# LEDboard_v0_2-R002.net
KiCad netlist of a schematic drawn in EAGLE
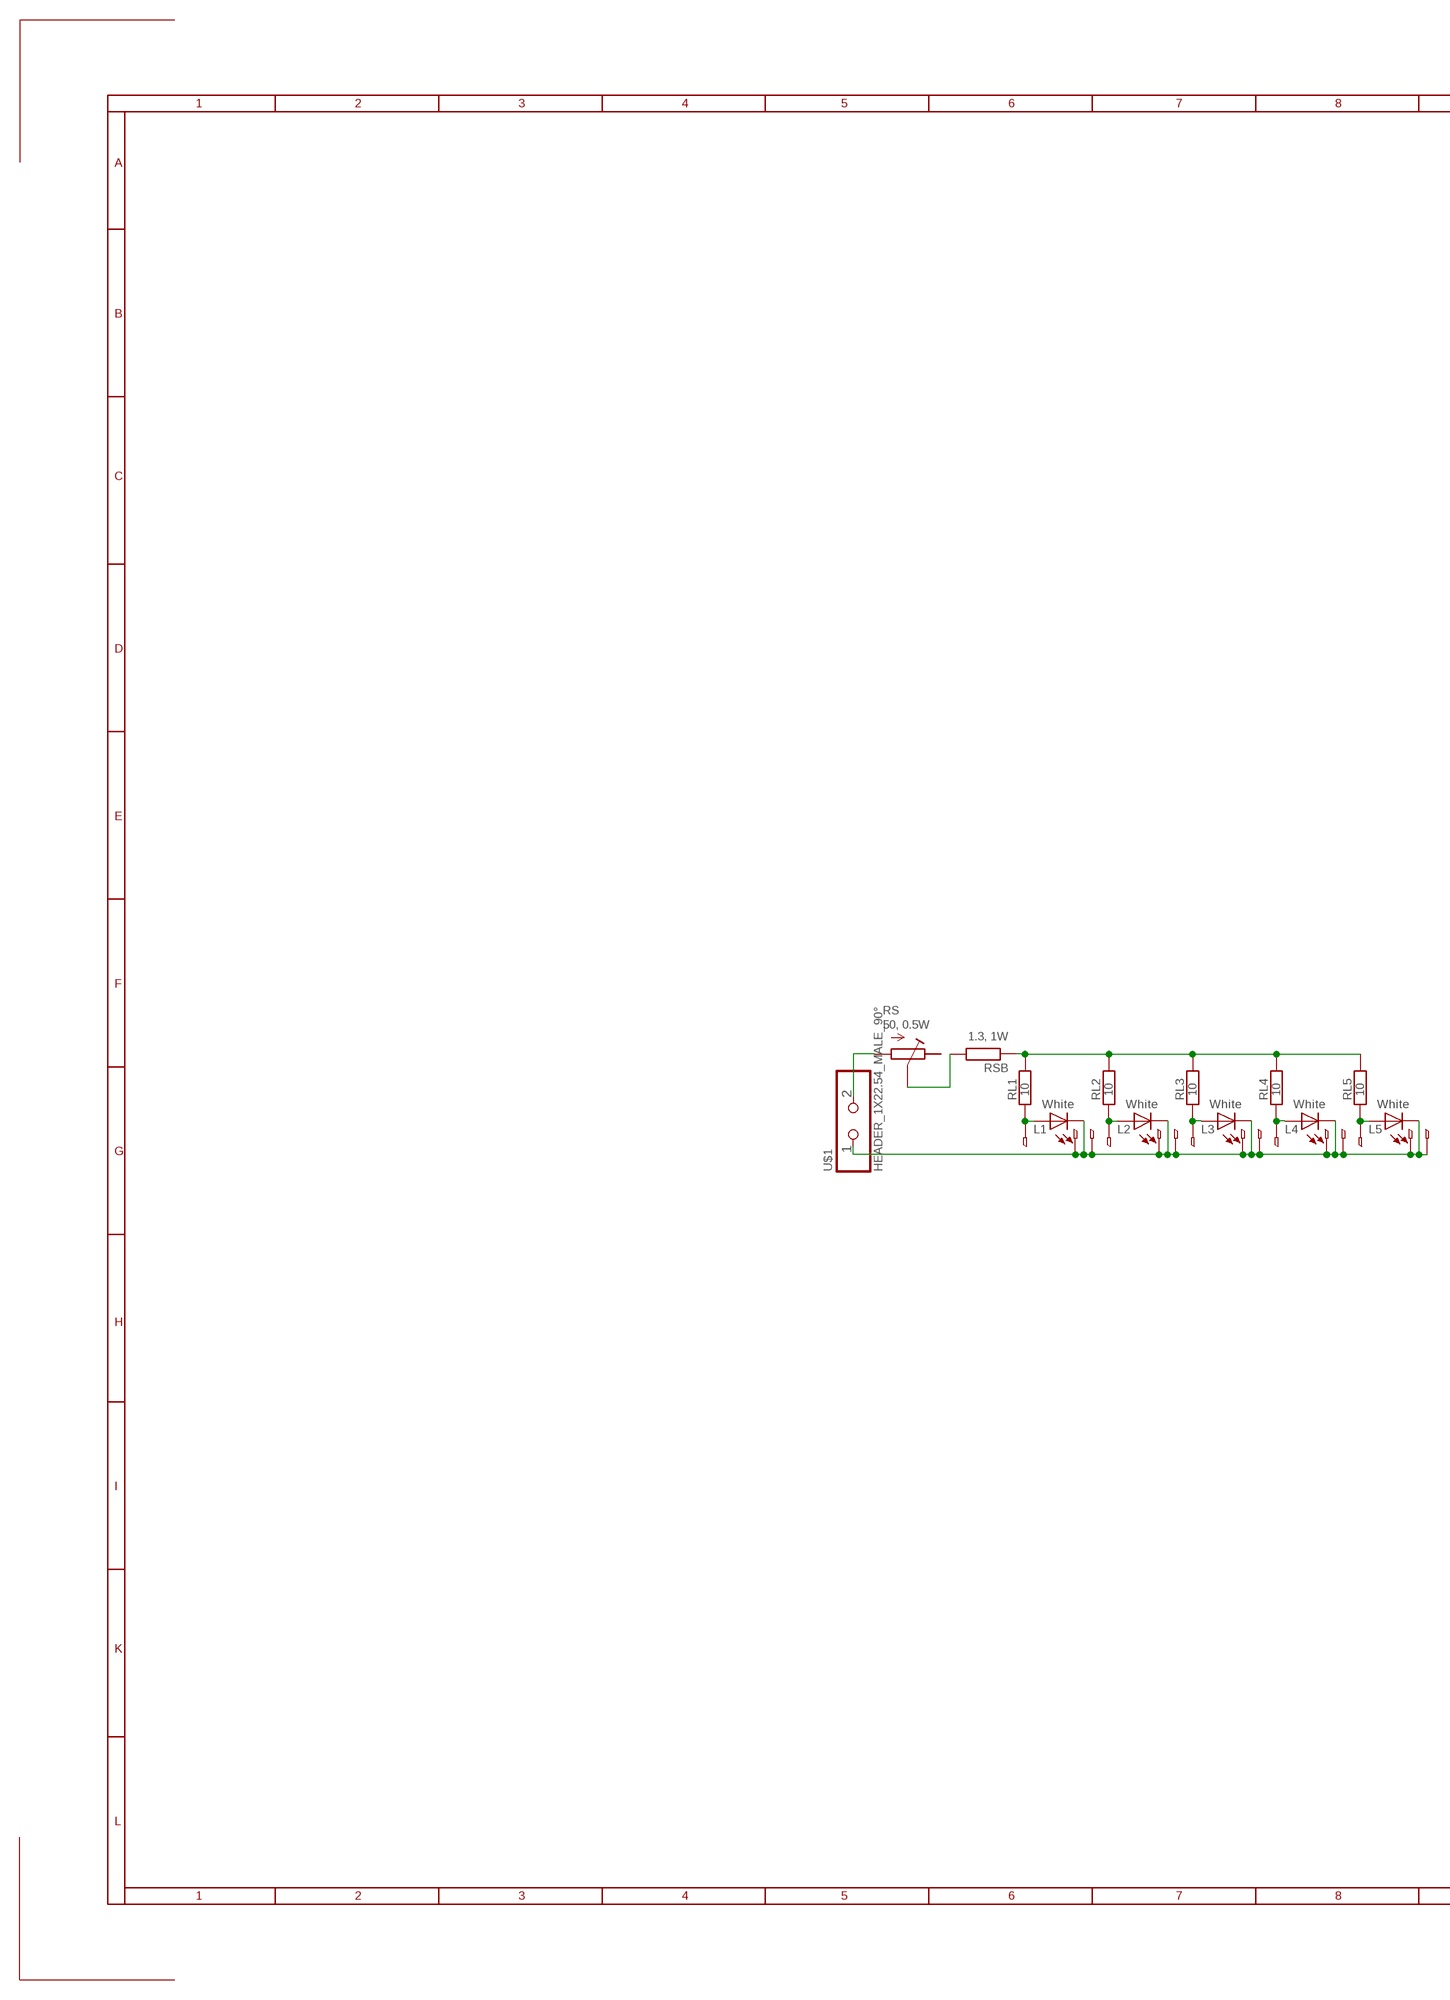
[diagram p0: schematic, sheet 1, part 1 of 2]
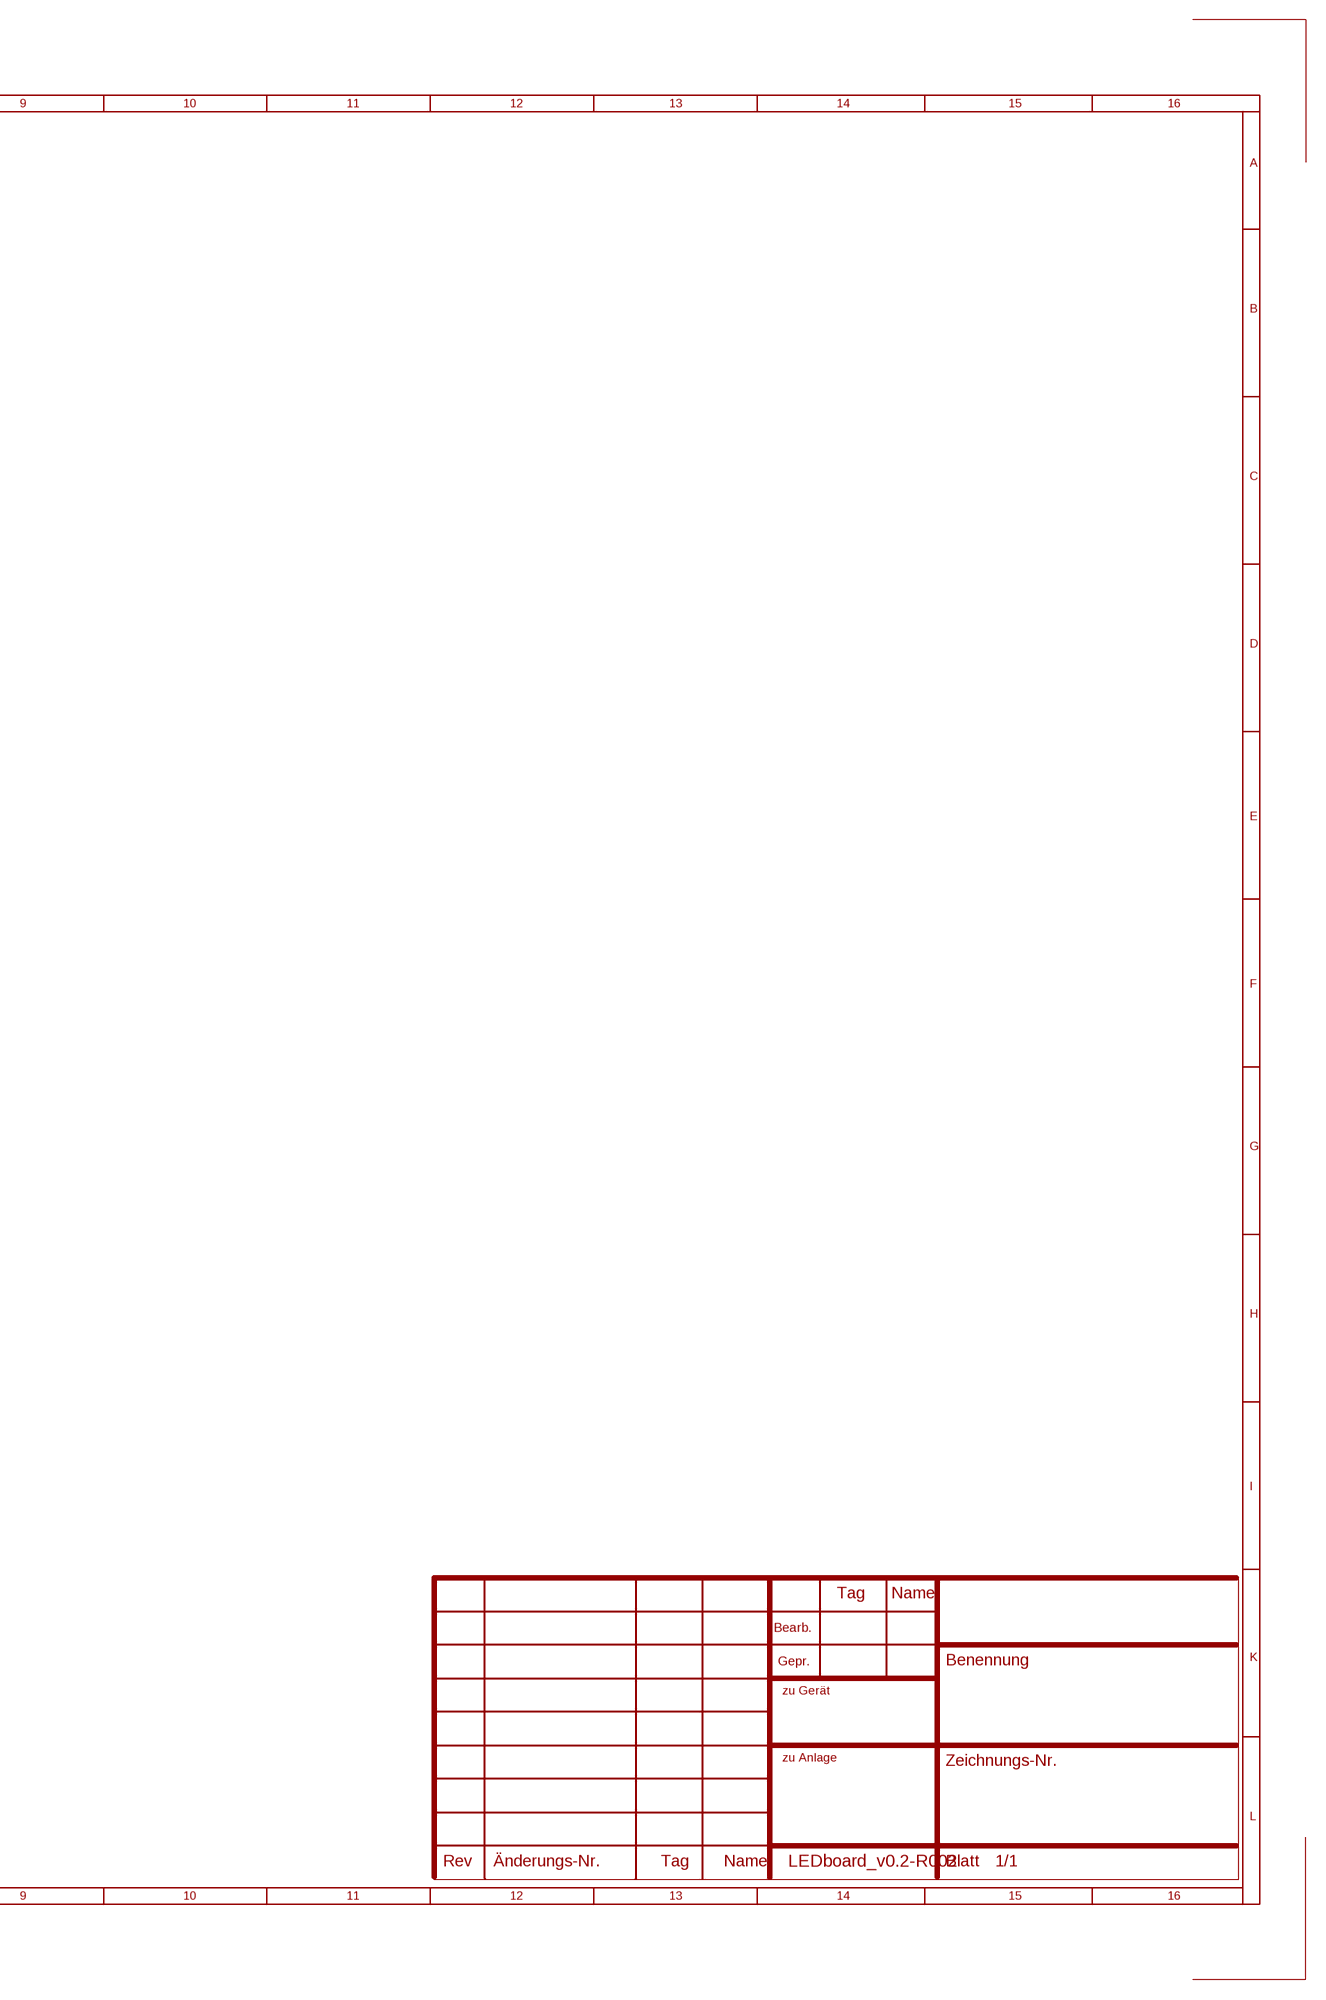
[diagram p1: schematic, sheet 1, part 2 of 2]

(export (version "E")
  (design (tool "Eeschema 10.0.6"))
  (components
    (comp (ref "L1")
      (value "White")
      (footprint "eagle-import:LED_LM561B")
      (libsource (lib "eagle-import") (part "LED_LM561B"))
    )
    (comp (ref "L2")
      (value "White")
      (footprint "eagle-import:LED_LM561B")
      (libsource (lib "eagle-import") (part "LED_LM561B"))
    )
    (comp (ref "L3")
      (value "White")
      (footprint "eagle-import:LED_LM561B")
      (libsource (lib "eagle-import") (part "LED_LM561B"))
    )
    (comp (ref "L4")
      (value "White")
      (footprint "eagle-import:LED_LM561B")
      (libsource (lib "eagle-import") (part "LED_LM561B"))
    )
    (comp (ref "L5")
      (value "White")
      (footprint "eagle-import:LED_LM561B")
      (libsource (lib "eagle-import") (part "LED_LM561B"))
    )
    (comp (ref "RL1")
      (value "10")
      (footprint "eagle-import:R0805")
      (libsource (lib "eagle-import") (part "R-EU_R0805"))
    )
    (comp (ref "RL2")
      (value "10")
      (footprint "eagle-import:R0805")
      (libsource (lib "eagle-import") (part "R-EU_R0805"))
    )
    (comp (ref "RL3")
      (value "10")
      (footprint "eagle-import:R0805")
      (libsource (lib "eagle-import") (part "R-EU_R0805"))
    )
    (comp (ref "RL4")
      (value "10")
      (footprint "eagle-import:R0805")
      (libsource (lib "eagle-import") (part "R-EU_R0805"))
    )
    (comp (ref "RL5")
      (value "10")
      (footprint "eagle-import:R0805")
      (libsource (lib "eagle-import") (part "R-EU_R0805"))
    )
    (comp (ref "RS")
      (value "50, 0.5W")
      (footprint "eagle-import:RTRIM3290H")
      (libsource (lib "eagle-import") (part "R-TRIMM3290H"))
    )
    (comp (ref "RSB")
      (value "1.3, 1W")
      (footprint "eagle-import:0207_10")
      (libsource (lib "eagle-import") (part "R-EU_0207/10"))
    )
    (comp (ref "U$1")
      (value "HEADER_1X22.54_MALE_90°")
      (footprint "eagle-import:1X02_2.54_90")
      (libsource (lib "eagle-import") (part "HEADER_1X22.54_MALE_90°"))
    )
  )
  (nets
    (net (code "1") (name "Net-(L1A-1)") (class "Default")
      (node (ref "L1") (pin "A1") (pinfunction "A_A1") (pintype "passive"))
      (node (ref "L1") (pin "A2") (pinfunction "1_A2") (pintype "passive"))
      (node (ref "RL1") (pin "1") (pinfunction "1_1") (pintype "passive"))
    )
    (net (code "2") (name "Net-(L1B-1)") (class "Default")
      (node (ref "L1") (pin "C1") (pinfunction "C_C1") (pintype "passive"))
      (node (ref "L1") (pin "C2") (pinfunction "1_C2") (pintype "passive"))
      (node (ref "L1") (pin "C3") (pinfunction "1_C3") (pintype "passive"))
      (node (ref "L2") (pin "C1") (pinfunction "C_C1") (pintype "passive"))
      (node (ref "L2") (pin "C2") (pinfunction "1_C2") (pintype "passive"))
      (node (ref "L2") (pin "C3") (pinfunction "1_C3") (pintype "passive"))
      (node (ref "L3") (pin "C1") (pinfunction "C_C1") (pintype "passive"))
      (node (ref "L3") (pin "C2") (pinfunction "1_C2") (pintype "passive"))
      (node (ref "L3") (pin "C3") (pinfunction "1_C3") (pintype "passive"))
      (node (ref "L4") (pin "C1") (pinfunction "C_C1") (pintype "passive"))
      (node (ref "L4") (pin "C2") (pinfunction "1_C2") (pintype "passive"))
      (node (ref "L4") (pin "C3") (pinfunction "1_C3") (pintype "passive"))
      (node (ref "L5") (pin "C1") (pinfunction "C_C1") (pintype "passive"))
      (node (ref "L5") (pin "C2") (pinfunction "1_C2") (pintype "passive"))
      (node (ref "L5") (pin "C3") (pinfunction "1_C3") (pintype "passive"))
      (node (ref "U$1") (pin "1") (pinfunction "1_1") (pintype "passive"))
    )
    (net (code "3") (name "Net-(L2A-1)") (class "Default")
      (node (ref "L2") (pin "A1") (pinfunction "A_A1") (pintype "passive"))
      (node (ref "L2") (pin "A2") (pinfunction "1_A2") (pintype "passive"))
      (node (ref "RL2") (pin "1") (pinfunction "1_1") (pintype "passive"))
    )
    (net (code "4") (name "Net-(L3A-1)") (class "Default")
      (node (ref "L3") (pin "A1") (pinfunction "A_A1") (pintype "passive"))
      (node (ref "L3") (pin "A2") (pinfunction "1_A2") (pintype "passive"))
      (node (ref "RL3") (pin "1") (pinfunction "1_1") (pintype "passive"))
    )
    (net (code "5") (name "Net-(L4A-1)") (class "Default")
      (node (ref "L4") (pin "A1") (pinfunction "A_A1") (pintype "passive"))
      (node (ref "L4") (pin "A2") (pinfunction "1_A2") (pintype "passive"))
      (node (ref "RL4") (pin "1") (pinfunction "1_1") (pintype "passive"))
    )
    (net (code "6") (name "Net-(L5A-1)") (class "Default")
      (node (ref "L5") (pin "A1") (pinfunction "A_A1") (pintype "passive"))
      (node (ref "L5") (pin "A2") (pinfunction "1_A2") (pintype "passive"))
      (node (ref "RL5") (pin "1") (pinfunction "1_1") (pintype "passive"))
    )
    (net (code "7") (name "Net-(RL1-Pad2)") (class "Default")
      (node (ref "RL1") (pin "2") (pinfunction "2_2") (pintype "passive"))
      (node (ref "RL2") (pin "2") (pinfunction "2_2") (pintype "passive"))
      (node (ref "RL3") (pin "2") (pinfunction "2_2") (pintype "passive"))
      (node (ref "RL4") (pin "2") (pinfunction "2_2") (pintype "passive"))
      (node (ref "RL5") (pin "2") (pinfunction "2_2") (pintype "passive"))
      (node (ref "RSB") (pin "1") (pinfunction "1_1") (pintype "passive"))
    )
    (net (code "8") (name "Net-(RS-E)") (class "Default")
      (node (ref "RS") (pin "1") (pinfunction "E_1") (pintype "passive"))
      (node (ref "U$1") (pin "2") (pinfunction "2_2") (pintype "passive"))
    )
    (net (code "9") (name "Net-(RS-S)") (class "Default")
      (node (ref "RS") (pin "2") (pinfunction "S_2") (pintype "passive"))
      (node (ref "RSB") (pin "2") (pinfunction "2_2") (pintype "passive"))
    )
    (net (code "10") (name "unconnected-(RS-A-Pad3)") (class "Default")
      (node (ref "RS") (pin "3") (pinfunction "A_3") (pintype "passive"))
    )
  )
)
